# Garagentor.net
KiCad netlist of a schematic drawn in EAGLE
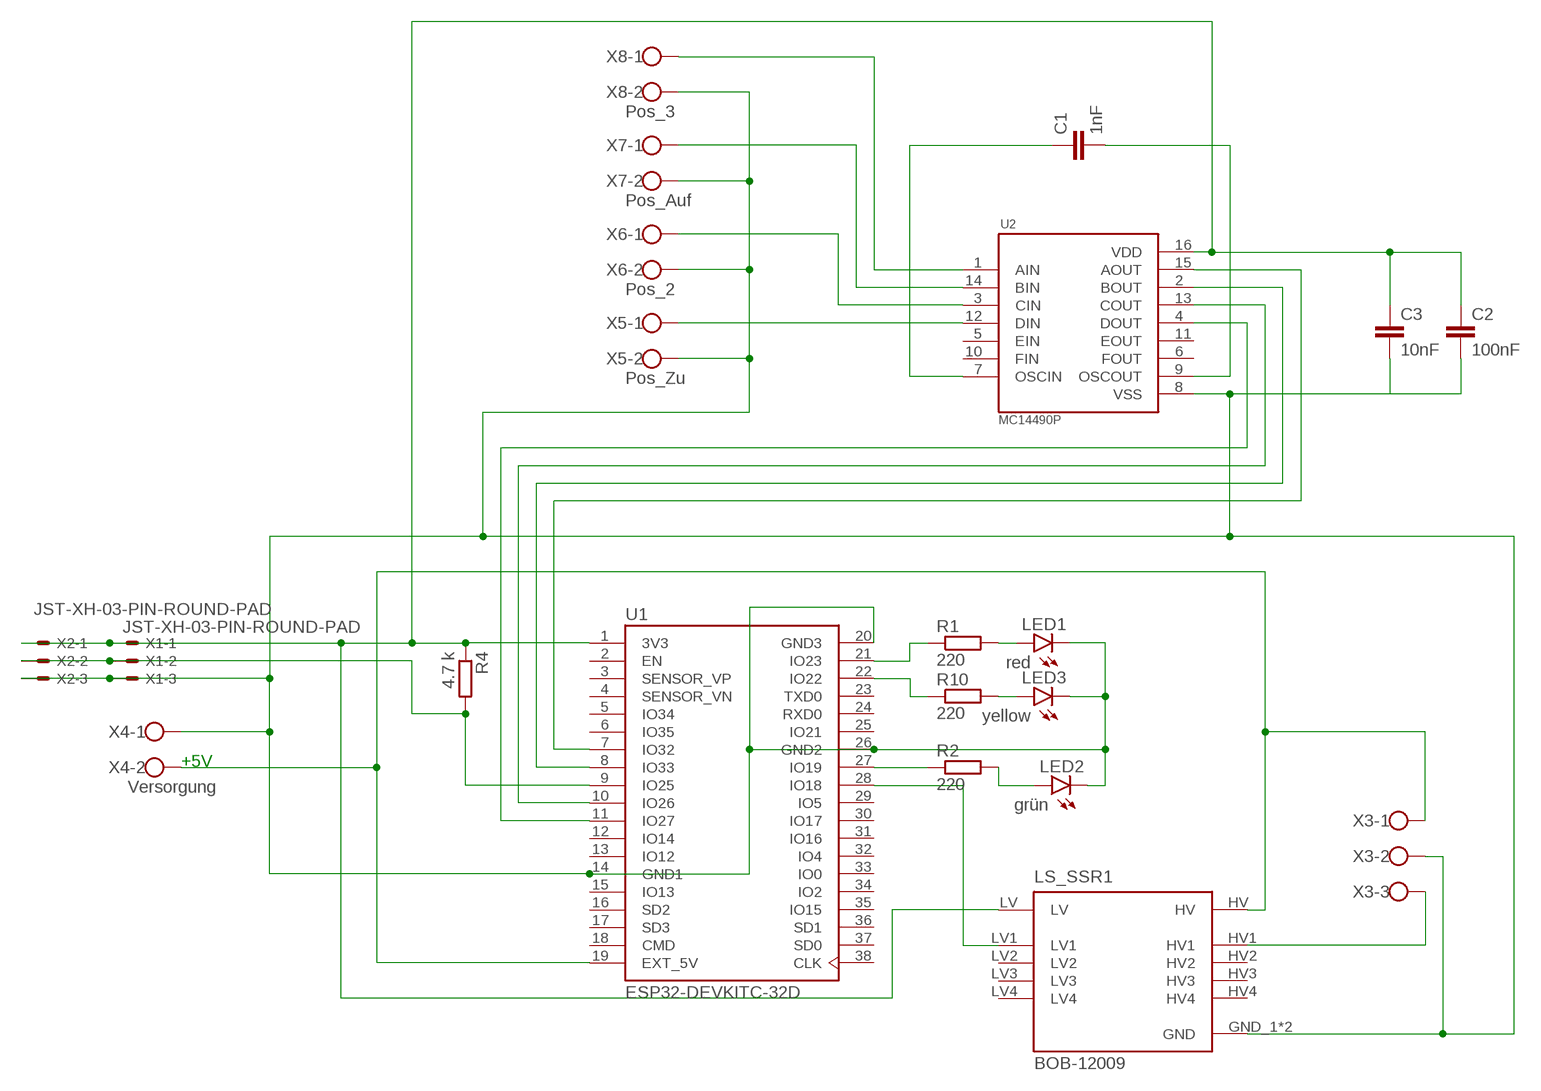
[diagram p0: schematic, sheet 1]

(export (version "E")
  (design (tool "Eeschema 10.0.6"))
  (components
    (comp (ref "C1")
      (value "1nF")
      (footprint "eagle-import:C050-024X044")
      (libsource (lib "eagle-import") (part "C-EU050-024X044"))
    )
    (comp (ref "C2")
      (value "100nF")
      (footprint "eagle-import:C050-024X044")
      (libsource (lib "eagle-import") (part "C-EU050-024X044"))
    )
    (comp (ref "C3")
      (value "10nF")
      (footprint "eagle-import:C050-024X044")
      (libsource (lib "eagle-import") (part "C-EU050-024X044"))
    )
    (comp (ref "LED1")
      (value "red")
      (footprint "eagle-import:LED3MM")
      (libsource (lib "eagle-import") (part "LED3MM"))
    )
    (comp (ref "LED2")
      (value "grün")
      (footprint "eagle-import:LED3MM")
      (libsource (lib "eagle-import") (part "LED3MM"))
    )
    (comp (ref "LED3")
      (value "yellow")
      (footprint "eagle-import:LED3MM")
      (libsource (lib "eagle-import") (part "LED3MM"))
    )
    (comp (ref "LS_SSR1")
      (value "BOB-12009")
      (footprint "eagle-import:CONV_BOB-12009")
      (fields (field (name "MF") "SparkFun"))
      (libsource (lib "eagle-import") (part "BOB-12009"))
    )
    (comp (ref "R1")
      (value "220")
      (footprint "eagle-import:0204_7")
      (libsource (lib "eagle-import") (part "R-EU_0204/7"))
    )
    (comp (ref "R2")
      (value "220")
      (footprint "eagle-import:0204_7")
      (libsource (lib "eagle-import") (part "R-EU_0204/7"))
    )
    (comp (ref "R4")
      (value "4.7 k")
      (footprint "eagle-import:0204_7")
      (libsource (lib "eagle-import") (part "R-EU_0204/7"))
    )
    (comp (ref "R10")
      (value "220")
      (footprint "eagle-import:0204_7")
      (libsource (lib "eagle-import") (part "R-EU_0204/7"))
    )
    (comp (ref "U1")
      (value "ESP32-DEVKITC-32D")
      (footprint "eagle-import:MODULE_ESP32-DEVKITC-32D")
      (fields (field (name "MF") "Espressif Systems"))
      (libsource (lib "eagle-import") (part "ESP32-DEVKITC-32D"))
    )
    (comp (ref "U2")
      (value "MC14490P")
      (footprint "eagle-import:DIP762W46P254L1918H444Q16P")
      (fields (field (name "MF") "onsemi"))
      (libsource (lib "eagle-import") (part "MC14490P"))
    )
    (comp (ref "X1")
      (value "JST-XH-03-PIN-ROUND-PAD")
      (footprint "eagle-import:JST-XH-03-PACKAGE-ROUND-PAD")
      (libsource (lib "eagle-import") (part "JST-XH-03-PIN-ROUND-PAD"))
    )
    (comp (ref "X2")
      (value "JST-XH-03-PIN-ROUND-PAD")
      (footprint "eagle-import:JST-XH-03-PACKAGE-ROUND-PAD")
      (libsource (lib "eagle-import") (part "JST-XH-03-PIN-ROUND-PAD"))
    )
    (comp (ref "X3")
      (value "W237-103")
      (footprint "eagle-import:W237-103")
      (fields (field (name "MPN") "237-103"))
      (libsource (lib "eagle-import") (part "W237-103"))
    )
    (comp (ref "X4")
      (value "Versorgung")
      (footprint "eagle-import:W237-102")
      (fields (field (name "MPN") "237-102"))
      (libsource (lib "eagle-import") (part "W237-102"))
    )
    (comp (ref "X5")
      (value "Pos_Zu")
      (footprint "eagle-import:W237-102")
      (fields (field (name "MPN") "237-102"))
      (libsource (lib "eagle-import") (part "W237-102"))
    )
    (comp (ref "X6")
      (value "Pos_2")
      (footprint "eagle-import:W237-102")
      (fields (field (name "MPN") "237-102"))
      (libsource (lib "eagle-import") (part "W237-102"))
    )
    (comp (ref "X7")
      (value "Pos_Auf")
      (footprint "eagle-import:W237-102")
      (fields (field (name "MPN") "237-102"))
      (libsource (lib "eagle-import") (part "W237-102"))
    )
    (comp (ref "X8")
      (value "Pos_3")
      (footprint "eagle-import:W237-102")
      (fields (field (name "MPN") "237-102"))
      (libsource (lib "eagle-import") (part "W237-102"))
    )
  )
  (nets
    (net (code "1") (name "Net-(LED1-C)") (class "Default")
      (node (ref "C2") (pin "2") (pinfunction "2_2") (pintype "passive"))
      (node (ref "C3") (pin "2") (pinfunction "2_2") (pintype "passive"))
      (node (ref "LED1") (pin "K") (pinfunction "C_K") (pintype "passive"))
      (node (ref "LED2") (pin "K") (pinfunction "C_K") (pintype "passive"))
      (node (ref "LED3") (pin "K") (pinfunction "C_K") (pintype "passive"))
      (node (ref "LS_SSR1") (pin "GND_1") (pinfunction "GND_GND_1") (pintype "power_in"))
      (node (ref "LS_SSR1") (pin "GND_2") (pinfunction "GND_GND_2") (pintype "power_in"))
      (node (ref "U1") (pin "14") (pinfunction "GND1_14") (pintype "power_in"))
      (node (ref "U1") (pin "20") (pinfunction "GND3_20") (pintype "power_in"))
      (node (ref "U1") (pin "26") (pinfunction "GND2_26") (pintype "power_in"))
      (node (ref "U2") (pin "8") (pinfunction "VSS_8") (pintype "power_in"))
      (node (ref "X1") (pin "3") (pinfunction "S_3") (pintype "passive"))
      (node (ref "X2") (pin "3") (pinfunction "S_3") (pintype "passive"))
      (node (ref "X3") (pin "2") (pinfunction "KL_2") (pintype "passive"))
      (node (ref "X4") (pin "1") (pinfunction "KL_1") (pintype "passive"))
      (node (ref "X5") (pin "2") (pinfunction "KL_2") (pintype "passive"))
      (node (ref "X6") (pin "2") (pinfunction "KL_2") (pintype "passive"))
      (node (ref "X7") (pin "2") (pinfunction "KL_2") (pintype "passive"))
      (node (ref "X8") (pin "2") (pinfunction "KL_2") (pintype "passive"))
    )
    (net (code "2") (name "Net-(LED1-PadA)") (class "Default")
      (node (ref "LED1") (pin "A") (pinfunction "A_A") (pintype "passive"))
      (node (ref "R1") (pin "2") (pinfunction "2_2") (pintype "passive"))
    )
    (net (code "3") (name "Net-(LED2-PadA)") (class "Default")
      (node (ref "LED2") (pin "A") (pinfunction "A_A") (pintype "passive"))
      (node (ref "R2") (pin "2") (pinfunction "2_2") (pintype "passive"))
    )
    (net (code "4") (name "Net-(LED3-PadA)") (class "Default")
      (node (ref "LED3") (pin "A") (pinfunction "A_A") (pintype "passive"))
      (node (ref "R10") (pin "2") (pinfunction "2_2") (pintype "passive"))
    )
    (net (code "5") (name "Net-(U1-3V3)") (class "Default")
      (node (ref "C2") (pin "1") (pinfunction "1_1") (pintype "passive"))
      (node (ref "C3") (pin "1") (pinfunction "1_1") (pintype "passive"))
      (node (ref "LS_SSR1") (pin "LV") (pinfunction "LV_LV") (pintype "bidirectional"))
      (node (ref "R4") (pin "1") (pinfunction "1_1") (pintype "passive"))
      (node (ref "U1") (pin "1") (pinfunction "3V3_1") (pintype "power_in"))
      (node (ref "U2") (pin "16") (pinfunction "VDD_16") (pintype "power_in"))
      (node (ref "X1") (pin "1") (pinfunction "S_1") (pintype "passive"))
      (node (ref "X2") (pin "1") (pinfunction "S_1") (pintype "passive"))
    )
    (net (code "6") (name "Net-(U1-EXT_5V)") (class "Default")
      (node (ref "LS_SSR1") (pin "HV") (pinfunction "HV_HV") (pintype "bidirectional"))
      (node (ref "U1") (pin "19") (pinfunction "EXT_5V_19") (pintype "power_in"))
      (node (ref "X3") (pin "1") (pinfunction "KL_1") (pintype "passive"))
      (node (ref "X4") (pin "2") (pinfunction "KL_2") (pintype "passive"))
    )
    (net (code "7") (name "Net-(U1-IO18)") (class "Default")
      (node (ref "LS_SSR1") (pin "LV1") (pinfunction "LV1_LV1") (pintype "bidirectional"))
      (node (ref "U1") (pin "28") (pinfunction "IO18_28") (pintype "bidirectional"))
    )
    (net (code "8") (name "Net-(U1-IO19)") (class "Default")
      (node (ref "R2") (pin "1") (pinfunction "1_1") (pintype "passive"))
      (node (ref "U1") (pin "27") (pinfunction "IO19_27") (pintype "bidirectional"))
    )
    (net (code "9") (name "Net-(U1-IO22)") (class "Default")
      (node (ref "R10") (pin "1") (pinfunction "1_1") (pintype "passive"))
      (node (ref "U1") (pin "22") (pinfunction "IO22_22") (pintype "bidirectional"))
    )
    (net (code "10") (name "Net-(U1-IO23)") (class "Default")
      (node (ref "R1") (pin "1") (pinfunction "1_1") (pintype "passive"))
      (node (ref "U1") (pin "21") (pinfunction "IO23_21") (pintype "bidirectional"))
    )
    (net (code "11") (name "Net-(U1-IO25)") (class "Default")
      (node (ref "R4") (pin "2") (pinfunction "2_2") (pintype "passive"))
      (node (ref "U1") (pin "9") (pinfunction "IO25_9") (pintype "bidirectional"))
      (node (ref "X1") (pin "2") (pinfunction "S_2") (pintype "passive"))
      (node (ref "X2") (pin "2") (pinfunction "S_2") (pintype "passive"))
    )
    (net (code "12") (name "Net-(U1-IO26)") (class "Default")
      (node (ref "U1") (pin "10") (pinfunction "IO26_10") (pintype "bidirectional"))
      (node (ref "U2") (pin "13") (pinfunction "COUT_13") (pintype "output"))
    )
    (net (code "13") (name "Net-(U1-IO27)") (class "Default")
      (node (ref "U1") (pin "11") (pinfunction "IO27_11") (pintype "bidirectional"))
      (node (ref "U2") (pin "4") (pinfunction "DOUT_4") (pintype "output"))
    )
    (net (code "14") (name "Net-(U1-IO32)") (class "Default")
      (node (ref "U1") (pin "7") (pinfunction "IO32_7") (pintype "bidirectional"))
      (node (ref "U2") (pin "15") (pinfunction "AOUT_15") (pintype "output"))
    )
    (net (code "15") (name "Net-(U1-IO33)") (class "Default")
      (node (ref "U1") (pin "8") (pinfunction "IO33_8") (pintype "bidirectional"))
      (node (ref "U2") (pin "2") (pinfunction "BOUT_2") (pintype "output"))
    )
    (net (code "16") (name "Net-(U2-AIN)") (class "Default")
      (node (ref "U2") (pin "1") (pinfunction "AIN_1") (pintype "input"))
      (node (ref "X8") (pin "1") (pinfunction "KL_1") (pintype "passive"))
    )
    (net (code "17") (name "Net-(U2-BIN)") (class "Default")
      (node (ref "U2") (pin "14") (pinfunction "BIN_14") (pintype "input"))
      (node (ref "X7") (pin "1") (pinfunction "KL_1") (pintype "passive"))
    )
    (net (code "18") (name "Net-(U2-CIN)") (class "Default")
      (node (ref "U2") (pin "3") (pinfunction "CIN_3") (pintype "input"))
      (node (ref "X6") (pin "1") (pinfunction "KL_1") (pintype "passive"))
    )
    (net (code "19") (name "Net-(U2-DIN)") (class "Default")
      (node (ref "U2") (pin "12") (pinfunction "DIN_12") (pintype "input"))
      (node (ref "X5") (pin "1") (pinfunction "KL_1") (pintype "passive"))
    )
    (net (code "20") (name "Net-(U2-OSCIN)") (class "Default")
      (node (ref "C1") (pin "1") (pinfunction "1_1") (pintype "passive"))
      (node (ref "U2") (pin "7") (pinfunction "OSCIN_7") (pintype "input"))
    )
    (net (code "21") (name "Net-(U2-OSCOUT)") (class "Default")
      (node (ref "C1") (pin "2") (pinfunction "2_2") (pintype "passive"))
      (node (ref "U2") (pin "9") (pinfunction "OSCOUT_9") (pintype "output"))
    )
    (net (code "22") (name "Net-(X3C-KL)") (class "Default")
      (node (ref "LS_SSR1") (pin "HV1") (pinfunction "HV1_HV1") (pintype "bidirectional"))
      (node (ref "X3") (pin "3") (pinfunction "KL_3") (pintype "passive"))
    )
    (net (code "23") (name "unconnected-(LS_SSR1-PadHV2)") (class "Default")
      (node (ref "LS_SSR1") (pin "HV2") (pinfunction "HV2_HV2") (pintype "bidirectional"))
    )
    (net (code "24") (name "unconnected-(LS_SSR1-PadHV3)") (class "Default")
      (node (ref "LS_SSR1") (pin "HV3") (pinfunction "HV3_HV3") (pintype "bidirectional"))
    )
    (net (code "25") (name "unconnected-(LS_SSR1-PadHV4)") (class "Default")
      (node (ref "LS_SSR1") (pin "HV4") (pinfunction "HV4_HV4") (pintype "bidirectional"))
    )
    (net (code "26") (name "unconnected-(LS_SSR1-PadLV2)") (class "Default")
      (node (ref "LS_SSR1") (pin "LV2") (pinfunction "LV2_LV2") (pintype "bidirectional"))
    )
    (net (code "27") (name "unconnected-(LS_SSR1-PadLV3)") (class "Default")
      (node (ref "LS_SSR1") (pin "LV3") (pinfunction "LV3_LV3") (pintype "bidirectional"))
    )
    (net (code "28") (name "unconnected-(LS_SSR1-PadLV4)") (class "Default")
      (node (ref "LS_SSR1") (pin "LV4") (pinfunction "LV4_LV4") (pintype "bidirectional"))
    )
    (net (code "29") (name "unconnected-(U1-CLK-Pad38)") (class "Default")
      (node (ref "U1") (pin "38") (pinfunction "CLK_38") (pintype "input"))
    )
    (net (code "30") (name "unconnected-(U1-CMD-Pad18)") (class "Default")
      (node (ref "U1") (pin "18") (pinfunction "CMD_18") (pintype "bidirectional"))
    )
    (net (code "31") (name "unconnected-(U1-EN-Pad2)") (class "Default")
      (node (ref "U1") (pin "2") (pinfunction "EN_2") (pintype "input"))
    )
    (net (code "32") (name "unconnected-(U1-IO0-Pad33)") (class "Default")
      (node (ref "U1") (pin "33") (pinfunction "IO0_33") (pintype "bidirectional"))
    )
    (net (code "33") (name "unconnected-(U1-IO2-Pad34)") (class "Default")
      (node (ref "U1") (pin "34") (pinfunction "IO2_34") (pintype "bidirectional"))
    )
    (net (code "34") (name "unconnected-(U1-IO4-Pad32)") (class "Default")
      (node (ref "U1") (pin "32") (pinfunction "IO4_32") (pintype "bidirectional"))
    )
    (net (code "35") (name "unconnected-(U1-IO5-Pad29)") (class "Default")
      (node (ref "U1") (pin "29") (pinfunction "IO5_29") (pintype "bidirectional"))
    )
    (net (code "36") (name "unconnected-(U1-IO12-Pad13)") (class "Default")
      (node (ref "U1") (pin "13") (pinfunction "IO12_13") (pintype "bidirectional"))
    )
    (net (code "37") (name "unconnected-(U1-IO13-Pad15)") (class "Default")
      (node (ref "U1") (pin "15") (pinfunction "IO13_15") (pintype "bidirectional"))
    )
    (net (code "38") (name "unconnected-(U1-IO14-Pad12)") (class "Default")
      (node (ref "U1") (pin "12") (pinfunction "IO14_12") (pintype "bidirectional"))
    )
    (net (code "39") (name "unconnected-(U1-IO15-Pad35)") (class "Default")
      (node (ref "U1") (pin "35") (pinfunction "IO15_35") (pintype "bidirectional"))
    )
    (net (code "40") (name "unconnected-(U1-IO16-Pad31)") (class "Default")
      (node (ref "U1") (pin "31") (pinfunction "IO16_31") (pintype "bidirectional"))
    )
    (net (code "41") (name "unconnected-(U1-IO17-Pad30)") (class "Default")
      (node (ref "U1") (pin "30") (pinfunction "IO17_30") (pintype "bidirectional"))
    )
    (net (code "42") (name "unconnected-(U1-IO21-Pad25)") (class "Default")
      (node (ref "U1") (pin "25") (pinfunction "IO21_25") (pintype "bidirectional"))
    )
    (net (code "43") (name "unconnected-(U1-IO34-Pad5)") (class "Default")
      (node (ref "U1") (pin "5") (pinfunction "IO34_5") (pintype "bidirectional"))
    )
    (net (code "44") (name "unconnected-(U1-IO35-Pad6)") (class "Default")
      (node (ref "U1") (pin "6") (pinfunction "IO35_6") (pintype "bidirectional"))
    )
    (net (code "45") (name "unconnected-(U1-RXD0-Pad24)") (class "Default")
      (node (ref "U1") (pin "24") (pinfunction "RXD0_24") (pintype "input"))
    )
    (net (code "46") (name "unconnected-(U1-SD0-Pad37)") (class "Default")
      (node (ref "U1") (pin "37") (pinfunction "SD0_37") (pintype "bidirectional"))
    )
    (net (code "47") (name "unconnected-(U1-SD1-Pad36)") (class "Default")
      (node (ref "U1") (pin "36") (pinfunction "SD1_36") (pintype "bidirectional"))
    )
    (net (code "48") (name "unconnected-(U1-SD2-Pad16)") (class "Default")
      (node (ref "U1") (pin "16") (pinfunction "SD2_16") (pintype "bidirectional"))
    )
    (net (code "49") (name "unconnected-(U1-SD3-Pad17)") (class "Default")
      (node (ref "U1") (pin "17") (pinfunction "SD3_17") (pintype "bidirectional"))
    )
    (net (code "50") (name "unconnected-(U1-SENSOR_VN-Pad4)") (class "Default")
      (node (ref "U1") (pin "4") (pinfunction "SENSOR_VN_4") (pintype "input"))
    )
    (net (code "51") (name "unconnected-(U1-SENSOR_VP-Pad3)") (class "Default")
      (node (ref "U1") (pin "3") (pinfunction "SENSOR_VP_3") (pintype "input"))
    )
    (net (code "52") (name "unconnected-(U1-TXD0-Pad23)") (class "Default")
      (node (ref "U1") (pin "23") (pinfunction "TXD0_23") (pintype "output"))
    )
    (net (code "53") (name "unconnected-(U2-EIN-Pad5)") (class "Default")
      (node (ref "U2") (pin "5") (pinfunction "EIN_5") (pintype "input"))
    )
    (net (code "54") (name "unconnected-(U2-EOUT-Pad11)") (class "Default")
      (node (ref "U2") (pin "11") (pinfunction "EOUT_11") (pintype "output"))
    )
    (net (code "55") (name "unconnected-(U2-FIN-Pad10)") (class "Default")
      (node (ref "U2") (pin "10") (pinfunction "FIN_10") (pintype "input"))
    )
    (net (code "56") (name "unconnected-(U2-FOUT-Pad6)") (class "Default")
      (node (ref "U2") (pin "6") (pinfunction "FOUT_6") (pintype "output"))
    )
  )
)
